# ISD1730.net
KiCad netlist of a schematic drawn in Altium Designer
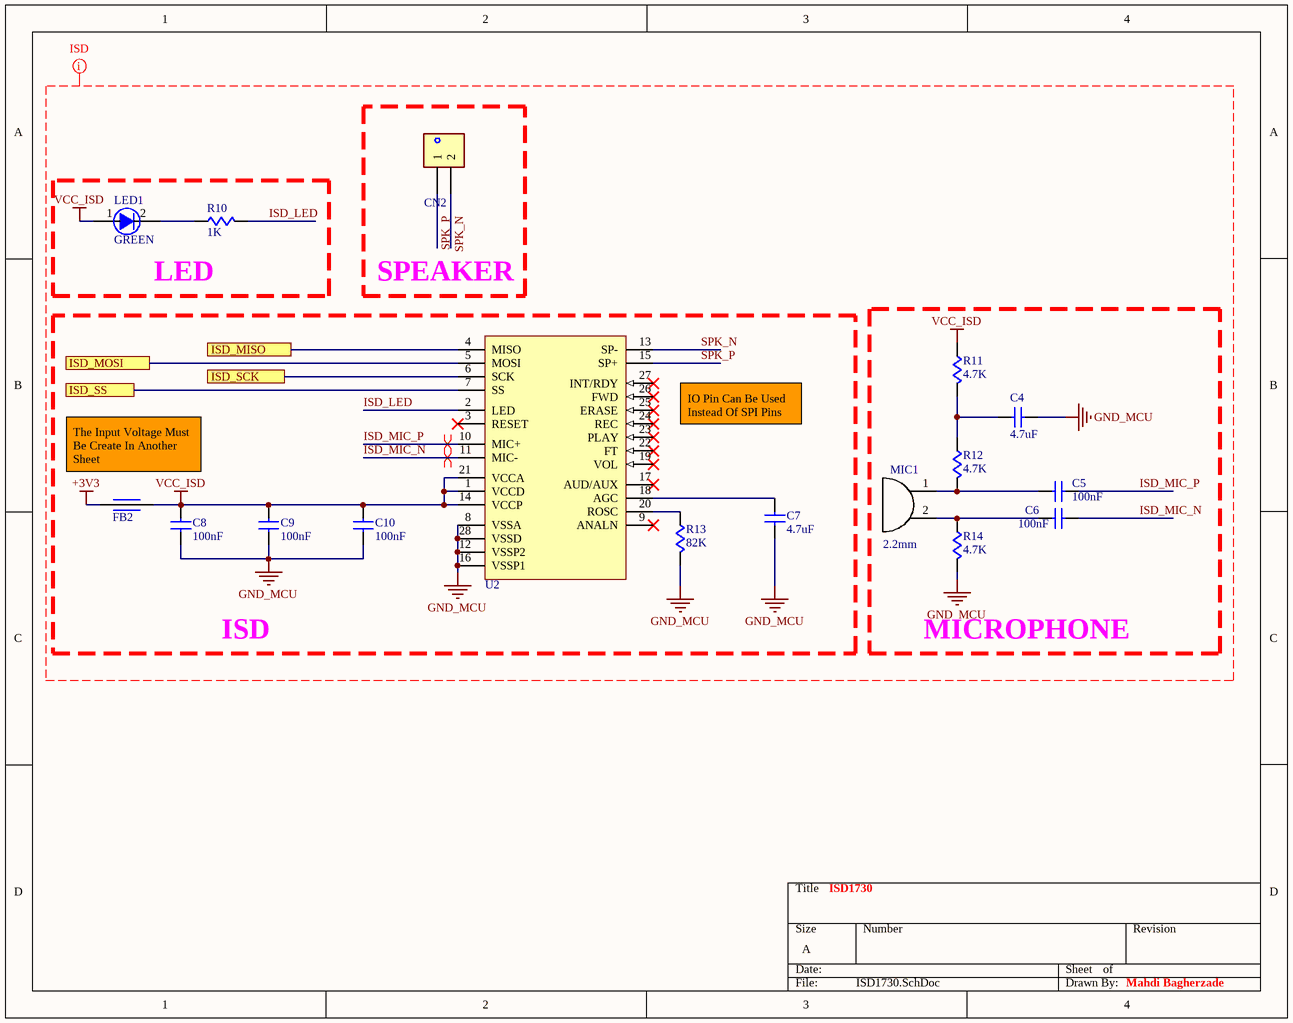
[diagram p0: ISD1730.SchDoc]

(export (version "E")
  (design (tool "Eeschema 10.0.6"))
  (components
    (comp (ref "C4")
      (value "4.7uF")
      (footprint "C-0805")
      (description "CAPACITOR")
      (fields
        (field (name "VOLTAGE") "50V")
        (field (name "TOLERANCE") "X7R")
        (field (name "PUBLISHER") "Mahdi Bagherzadeh")
      )
      (libsource (lib "Mahdi-Bagherzadeh") (part "CAP-CER"))
    )
    (comp (ref "C5")
      (value "100nF")
      (footprint "C-0805")
      (description "CAPACITOR")
      (fields
        (field (name "VOLTAGE") "50V")
        (field (name "TOLERANCE") "X7R")
        (field (name "PUBLISHER") "Mahdi Bagherzadeh")
      )
      (libsource (lib "Mahdi-Bagherzadeh") (part "CAP-CER"))
    )
    (comp (ref "C6")
      (value "100nF")
      (footprint "C-0805")
      (description "CAPACITOR")
      (fields
        (field (name "VOLTAGE") "50V")
        (field (name "TOLERANCE") "X7R")
        (field (name "PUBLISHER") "Mahdi Bagherzadeh")
      )
      (libsource (lib "Mahdi-Bagherzadeh") (part "CAP-CER"))
    )
    (comp (ref "C7")
      (value "4.7uF")
      (footprint "C-0805")
      (description "CAPACITOR")
      (fields
        (field (name "VOLTAGE") "50V")
        (field (name "TOLERANCE") "X7R")
        (field (name "PUBLISHER") "Mahdi Bagherzadeh")
      )
      (libsource (lib "Mahdi-Bagherzadeh") (part "CAP-CER"))
    )
    (comp (ref "C8")
      (value "100nF")
      (footprint "C-0805")
      (description "CAPACITOR")
      (fields
        (field (name "VOLTAGE") "50V")
        (field (name "TOLERANCE") "X7R")
        (field (name "PUBLISHER") "Mahdi Bagherzadeh")
      )
      (libsource (lib "Mahdi-Bagherzadeh") (part "CAP-CER"))
    )
    (comp (ref "C9")
      (value "100nF")
      (footprint "C-0805")
      (description "CAPACITOR")
      (fields
        (field (name "VOLTAGE") "50V")
        (field (name "TOLERANCE") "X7R")
        (field (name "PUBLISHER") "Mahdi Bagherzadeh")
      )
      (libsource (lib "Mahdi-Bagherzadeh") (part "CAP-CER"))
    )
    (comp (ref "C10")
      (value "100nF")
      (footprint "C-0805")
      (description "CAPACITOR")
      (fields
        (field (name "VOLTAGE") "50V")
        (field (name "TOLERANCE") "X7R")
        (field (name "PUBLISHER") "Mahdi Bagherzadeh")
      )
      (libsource (lib "Mahdi-Bagherzadeh") (part "CAP-CER"))
    )
    (comp (ref "CN2")
      (value "Connector XH-2-Straight-THD-2.54mm")
      (footprint "XH-2")
      (description "CONNECTOR")
      (fields (field (name "PUBLISHER") "Mahdi Bagherzadeh"))
      (libsource (lib "Mahdi-Bagherzadeh") (part "CN-2pin"))
    )
    (comp (ref "FB2")
      (value "Ferrite Bead SMD")
      (footprint "FB-0805")
      (description "INDUCATOR")
      (fields (field (name "PUBLISHER") "Mahdi Bagherzadeh"))
      (libsource (lib "Mahdi-Bagherzadeh") (part "FERRITE BEAD"))
    )
    (comp (ref "LED1")
      (value "LED GREEN-1206-SMD")
      (footprint "LED-1206-Y")
      (description "LED")
      (fields (field (name "COLOR") "GREEN") (field (name "PUBLISHER") "Mahdi Bagherzadeh"))
      (libsource (lib "Mahdi-Bagherzadeh") (part "LED"))
    )
    (comp (ref "MIC1")
      (value "Mic 2.2mm-THD")
      (footprint "MIC-2.2mm")
      (description "MIC")
      (fields (field (name "SIZE") "2.2mm") (field (name "PUBLISHER") "Mahdi Bagherzadeh"))
      (libsource (lib "Mahdi-Bagherzadeh") (part "MIC"))
    )
    (comp (ref "R10")
      (value "1K")
      (footprint "R-0805")
      (description "RESISTOR")
      (fields
        (field (name "POWER") "1/8W")
        (field (name "TOLERANCE") "5%")
        (field (name "PUBLISHER") "Mahdi Bagherzadeh")
      )
      (libsource (lib "Mahdi-Bagherzadeh") (part "RES"))
    )
    (comp (ref "R11")
      (value "4.7K")
      (footprint "R-0805")
      (description "RESISTOR")
      (fields
        (field (name "POWER") "1/8W")
        (field (name "TOLERANCE") "5%")
        (field (name "PUBLISHER") "Mahdi Bagherzadeh")
      )
      (libsource (lib "Mahdi-Bagherzadeh") (part "RES"))
    )
    (comp (ref "R12")
      (value "4.7K")
      (footprint "R-0805")
      (description "RESISTOR")
      (fields
        (field (name "POWER") "1/8W")
        (field (name "TOLERANCE") "5%")
        (field (name "PUBLISHER") "Mahdi Bagherzadeh")
      )
      (libsource (lib "Mahdi-Bagherzadeh") (part "RES"))
    )
    (comp (ref "R13")
      (value "82K")
      (footprint "R-0805")
      (description "RESISTOR")
      (fields
        (field (name "POWER") "1/8W")
        (field (name "TOLERANCE") "5%")
        (field (name "PUBLISHER") "Mahdi Bagherzadeh")
      )
      (libsource (lib "Mahdi-Bagherzadeh") (part "RES"))
    )
    (comp (ref "R14")
      (value "4.7K")
      (footprint "R-0805")
      (description "RESISTOR")
      (fields
        (field (name "POWER") "1/8W")
        (field (name "TOLERANCE") "5%")
        (field (name "PUBLISHER") "Mahdi Bagherzadeh")
      )
      (libsource (lib "Mahdi-Bagherzadeh") (part "RES"))
    )
    (comp (ref "U2")
      (value "IC ISD1730-SMD")
      (footprint "SOIC28-wide")
      (description "IC")
      (fields (field (name "PUBLISHER") "Mahdi Bagherzadeh"))
      (libsource (lib "Mahdi-Bagherzadeh") (part "ISD1730"))
    )
  )
  (nets
    (net (code "1") (name "+3V3") (class "Default")
      (node (ref "FB2") (pin "1") (pinfunction "1_1") (pintype "passive"))
    )
    (net (code "2") (name "/ISD_LED") (class "Default")
      (node (ref "R10") (pin "2") (pinfunction "2_2") (pintype "passive"))
      (node (ref "U2") (pin "2") (pinfunction "LED_2") (pintype "passive"))
    )
    (net (code "3") (name "/ISD_MIC_N") (class "Default")
      (node (ref "C6") (pin "2") (pinfunction "2_2") (pintype "passive"))
      (node (ref "U2") (pin "11") (pinfunction "MIC-_11") (pintype "passive"))
    )
    (net (code "4") (name "/ISD_MIC_P") (class "Default")
      (node (ref "C5") (pin "2") (pinfunction "2_2") (pintype "passive"))
      (node (ref "U2") (pin "10") (pinfunction "MIC+_10") (pintype "passive"))
    )
    (net (code "5") (name "/ISD_MISO") (class "Default")
      (node (ref "U2") (pin "4") (pinfunction "MISO_4") (pintype "passive"))
    )
    (net (code "6") (name "/ISD_MOSI") (class "Default")
      (node (ref "U2") (pin "5") (pinfunction "MOSI_5") (pintype "passive"))
    )
    (net (code "7") (name "/ISD_SCK") (class "Default")
      (node (ref "U2") (pin "6") (pinfunction "SCK_6") (pintype "passive"))
    )
    (net (code "8") (name "/ISD_SS") (class "Default")
      (node (ref "U2") (pin "7") (pinfunction "SS_7") (pintype "passive"))
    )
    (net (code "9") (name "/SPK_N") (class "Default")
      (node (ref "CN2") (pin "2") (pinfunction "2_2") (pintype "passive"))
      (node (ref "U2") (pin "13") (pinfunction "SP-_13") (pintype "passive"))
    )
    (net (code "10") (name "/SPK_P") (class "Default")
      (node (ref "CN2") (pin "1") (pinfunction "1_1") (pintype "passive"))
      (node (ref "U2") (pin "15") (pinfunction "SP+_15") (pintype "passive"))
    )
    (net (code "11") (name "GND_MCU") (class "Default")
      (node (ref "C10") (pin "2") (pinfunction "2_2") (pintype "passive"))
      (node (ref "C4") (pin "2") (pinfunction "2_2") (pintype "passive"))
      (node (ref "C7") (pin "2") (pinfunction "2_2") (pintype "passive"))
      (node (ref "C8") (pin "2") (pinfunction "2_2") (pintype "passive"))
      (node (ref "C9") (pin "2") (pinfunction "2_2") (pintype "passive"))
      (node (ref "R13") (pin "2") (pinfunction "2_2") (pintype "passive"))
      (node (ref "R14") (pin "2") (pinfunction "2_2") (pintype "passive"))
      (node (ref "U2") (pin "12") (pinfunction "VSSP2_12") (pintype "power_in"))
      (node (ref "U2") (pin "16") (pinfunction "VSSP1_16") (pintype "power_in"))
      (node (ref "U2") (pin "28") (pinfunction "VSSD_28") (pintype "power_in"))
      (node (ref "U2") (pin "8") (pinfunction "VSSA_8") (pintype "power_in"))
    )
    (net (code "12") (name "Net-(C4-Pad1)") (class "Default")
      (node (ref "C4") (pin "1") (pinfunction "1_1") (pintype "passive"))
      (node (ref "R11") (pin "2") (pinfunction "2_2") (pintype "passive"))
      (node (ref "R12") (pin "1") (pinfunction "1_1") (pintype "passive"))
    )
    (net (code "13") (name "Net-(C5-Pad1)") (class "Default")
      (node (ref "C5") (pin "1") (pinfunction "1_1") (pintype "passive"))
      (node (ref "MIC1") (pin "1") (pinfunction "1_1") (pintype "passive"))
      (node (ref "R12") (pin "2") (pinfunction "2_2") (pintype "passive"))
    )
    (net (code "14") (name "Net-(C6-Pad1)") (class "Default")
      (node (ref "C6") (pin "1") (pinfunction "1_1") (pintype "passive"))
      (node (ref "MIC1") (pin "2") (pinfunction "2_2") (pintype "passive"))
      (node (ref "R14") (pin "1") (pinfunction "1_1") (pintype "passive"))
    )
    (net (code "15") (name "Net-(LED1-C)") (class "Default")
      (node (ref "LED1") (pin "2") (pinfunction "C_2") (pintype "passive"))
      (node (ref "R10") (pin "1") (pinfunction "1_1") (pintype "passive"))
    )
    (net (code "16") (name "Net-(U2-AGC)") (class "Default")
      (node (ref "C7") (pin "1") (pinfunction "1_1") (pintype "passive"))
      (node (ref "U2") (pin "18") (pinfunction "AGC_18") (pintype "passive"))
    )
    (net (code "17") (name "Net-(U2-ROSC)") (class "Default")
      (node (ref "R13") (pin "1") (pinfunction "1_1") (pintype "passive"))
      (node (ref "U2") (pin "20") (pinfunction "ROSC_20") (pintype "passive"))
    )
    (net (code "18") (name "VCC_ISD") (class "Default")
      (node (ref "C10") (pin "1") (pinfunction "1_1") (pintype "passive"))
      (node (ref "C8") (pin "1") (pinfunction "1_1") (pintype "passive"))
      (node (ref "C9") (pin "1") (pinfunction "1_1") (pintype "passive"))
      (node (ref "FB2") (pin "2") (pinfunction "2_2") (pintype "passive"))
      (node (ref "LED1") (pin "1") (pinfunction "A_1") (pintype "passive"))
      (node (ref "R11") (pin "1") (pinfunction "1_1") (pintype "passive"))
      (node (ref "U2") (pin "1") (pinfunction "VCCD_1") (pintype "power_in"))
      (node (ref "U2") (pin "14") (pinfunction "VCCP_14") (pintype "power_in"))
      (node (ref "U2") (pin "21") (pinfunction "VCCA_21") (pintype "power_in"))
    )
    (net (code "19") (name "unconnected-(U2-ANALN-Pad9)") (class "Default")
      (node (ref "U2") (pin "9") (pinfunction "ANALN_9") (pintype "passive+no_connect"))
    )
    (net (code "20") (name "unconnected-(U2-AUD{slash}AUX-Pad17)") (class "Default")
      (node (ref "U2") (pin "17") (pinfunction "AUD/AUX_17") (pintype "passive+no_connect"))
    )
    (net (code "21") (name "unconnected-(U2-ERASE-Pad25)") (class "Default")
      (node (ref "U2") (pin "25") (pinfunction "ERASE_25") (pintype "input+no_connect"))
    )
    (net (code "22") (name "unconnected-(U2-FT-Pad22)") (class "Default")
      (node (ref "U2") (pin "22") (pinfunction "FT_22") (pintype "input+no_connect"))
    )
    (net (code "23") (name "unconnected-(U2-FWD-Pad26)") (class "Default")
      (node (ref "U2") (pin "26") (pinfunction "FWD_26") (pintype "input+no_connect"))
    )
    (net (code "24") (name "unconnected-(U2-INT{slash}RDY-Pad27)") (class "Default")
      (node (ref "U2") (pin "27") (pinfunction "INT/RDY_27") (pintype "input+no_connect"))
    )
    (net (code "25") (name "unconnected-(U2-PLAY-Pad23)") (class "Default")
      (node (ref "U2") (pin "23") (pinfunction "PLAY_23") (pintype "input+no_connect"))
    )
    (net (code "26") (name "unconnected-(U2-REC-Pad24)") (class "Default")
      (node (ref "U2") (pin "24") (pinfunction "REC_24") (pintype "input+no_connect"))
    )
    (net (code "27") (name "unconnected-(U2-RESET-Pad3)") (class "Default")
      (node (ref "U2") (pin "3") (pinfunction "RESET_3") (pintype "passive+no_connect"))
    )
    (net (code "28") (name "unconnected-(U2-VOL-Pad19)") (class "Default")
      (node (ref "U2") (pin "19") (pinfunction "VOL_19") (pintype "input+no_connect"))
    )
  )
)
